# Snip_Power.net
KiCad netlist of a schematic drawn in Altium Designer
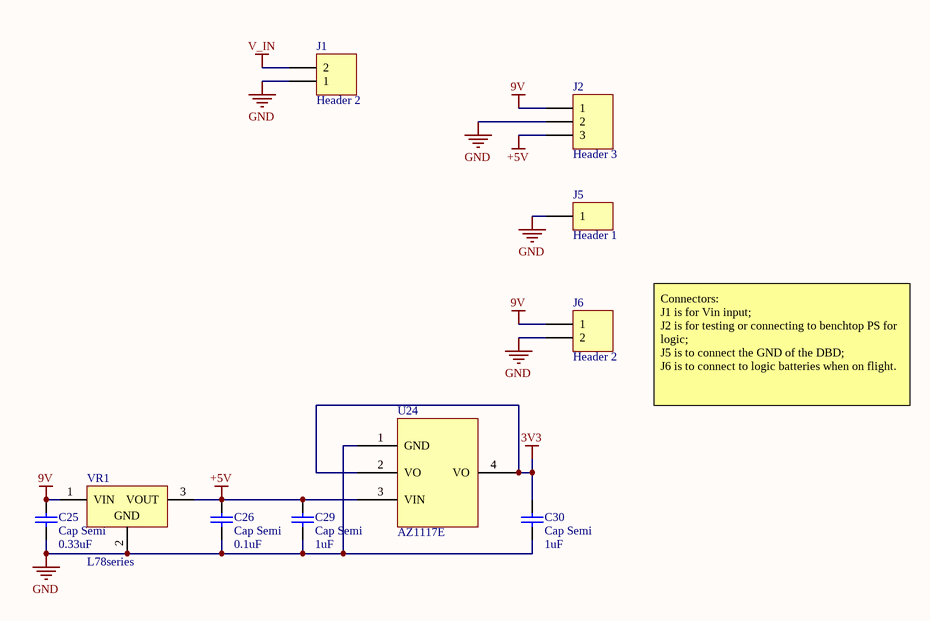
[diagram p0: Snip_Power.SchDoc]

(export (version "E")
  (design (tool "Eeschema 10.0.6"))
  (components
    (comp (ref "C25")
      (value "Cap Semi")
      (footprint "C1206")
      (description "Capacitor (Semiconductor SIM Model)")
      (fields (field (name "ALTIUM_VALUE") "0.33uF") (field (name "PUBLISHER") "Altium Limited"))
      (libsource (lib "Miscellaneous Devices") (part "Cap Semi"))
    )
    (comp (ref "C26")
      (value "Cap Semi")
      (footprint "C1206")
      (description "Capacitor (Semiconductor SIM Model)")
      (fields (field (name "ALTIUM_VALUE") "0.1uF") (field (name "PUBLISHER") "Altium Limited"))
      (libsource (lib "Miscellaneous Devices") (part "Cap Semi"))
    )
    (comp (ref "C29")
      (value "Cap Semi")
      (footprint "C1206")
      (description "Capacitor (Semiconductor SIM Model)")
      (fields (field (name "ALTIUM_VALUE") "1uF") (field (name "PUBLISHER") "Altium Limited"))
      (libsource (lib "Miscellaneous Devices") (part "Cap Semi"))
    )
    (comp (ref "C30")
      (value "Cap Semi")
      (footprint "C1206")
      (description "Capacitor (Semiconductor SIM Model)")
      (fields (field (name "ALTIUM_VALUE") "1uF") (field (name "PUBLISHER") "Altium Limited"))
      (libsource (lib "Miscellaneous Devices") (part "Cap Semi"))
    )
    (comp (ref "J1")
      (value "Header 2")
      (footprint "PheonixContact_1757242")
      (description "Header, 2-Pin")
      (fields (field (name "PUBLISHER") "Altium Limited"))
      (libsource (lib "SCMLI_V3_1") (part "Header 2"))
    )
    (comp (ref "J2")
      (value "Header 3")
      (footprint "3_test_pin")
      (description "Header, 3-Pin")
      (fields (field (name "PUBLISHER") "Altium Limited"))
      (libsource (lib "SCMLI_V3_1") (part "Header 3"))
    )
    (comp (ref "J5")
      (value "Header 1")
      (footprint "GNDOUT")
      (description "Header, 1-Pin")
      (fields (field (name "PUBLISHER") "Altium Limited"))
      (libsource (lib "SCMLI_V3_1") (part "Header 1"))
    )
    (comp (ref "J6")
      (value "Header 2")
      (footprint "BatteryConnector_Molex_1720640002")
      (description "Header, 2-Pin")
      (fields (field (name "PUBLISHER") "Altium Limited"))
      (libsource (lib "") (part "Header 2_1"))
    )
    (comp (ref "U24") (value "AZ1117E") (footprint "SOT223") (libsource (lib "SCMLI_V3_1") (part "AZ1117E")))
    (comp (ref "VR1")
      (value "L78series")
      (footprint "L78_TO220_3")
      (description "Positive Voltage Regulator")
      (libsource (lib "SCMLI_V3_1") (part "PM-REG-L78"))
    )
  )
  (nets
    (net (code "1") (name "+5V") (class "Default")
      (node (ref "C26") (pin "2") (pinfunction "2_2") (pintype "passive"))
      (node (ref "C29") (pin "2") (pinfunction "2_2") (pintype "passive"))
      (node (ref "J2") (pin "3") (pinfunction "3_3") (pintype "passive"))
      (node (ref "U24") (pin "3") (pinfunction "VIN_3") (pintype "passive"))
      (node (ref "VR1") (pin "3") (pinfunction "VOUT_3") (pintype "power_in"))
    )
    (net (code "2") (name "3V3") (class "Default")
      (node (ref "C30") (pin "2") (pinfunction "2_2") (pintype "passive"))
      (node (ref "U24") (pin "2") (pinfunction "VO_2") (pintype "passive"))
      (node (ref "U24") (pin "4") (pinfunction "VO_4") (pintype "passive"))
    )
    (net (code "3") (name "9V") (class "Default")
      (node (ref "C25") (pin "2") (pinfunction "2_2") (pintype "passive"))
      (node (ref "J2") (pin "1") (pinfunction "1_1") (pintype "passive"))
      (node (ref "J6") (pin "1") (pinfunction "1_1") (pintype "passive"))
      (node (ref "VR1") (pin "1") (pinfunction "VIN_1") (pintype "power_in"))
    )
    (net (code "4") (name "GND") (class "Default")
      (node (ref "C25") (pin "1") (pinfunction "1_1") (pintype "passive"))
      (node (ref "C26") (pin "1") (pinfunction "1_1") (pintype "passive"))
      (node (ref "C29") (pin "1") (pinfunction "1_1") (pintype "passive"))
      (node (ref "C30") (pin "1") (pinfunction "1_1") (pintype "passive"))
      (node (ref "J1") (pin "1") (pinfunction "1_1") (pintype "passive"))
      (node (ref "J2") (pin "2") (pinfunction "2_2") (pintype "passive"))
      (node (ref "J5") (pin "1") (pinfunction "1_1") (pintype "passive"))
      (node (ref "J6") (pin "2") (pinfunction "2_2") (pintype "passive"))
      (node (ref "U24") (pin "1") (pinfunction "GND_1") (pintype "passive"))
      (node (ref "VR1") (pin "2") (pinfunction "GND_2") (pintype "power_in"))
    )
    (net (code "5") (name "V_IN") (class "Default")
      (node (ref "J1") (pin "2") (pinfunction "2_2") (pintype "passive"))
    )
  )
)
